# Sheet2.net
KiCad netlist of a schematic drawn in Altium Designer
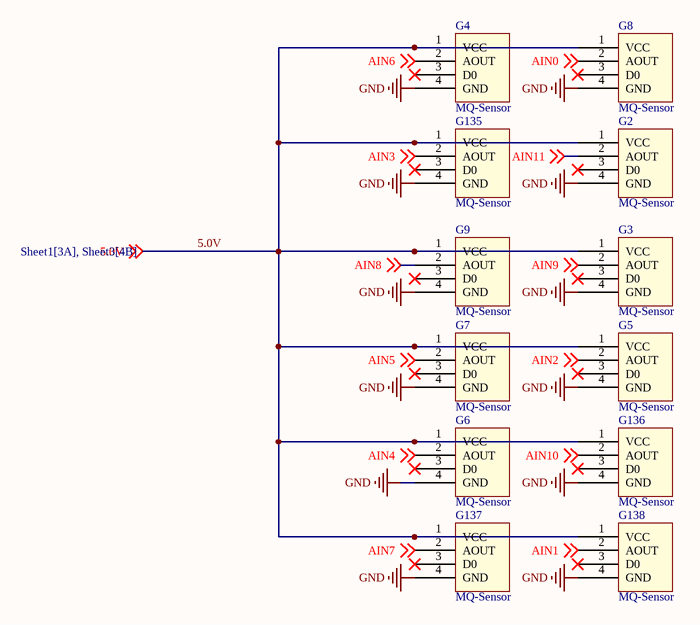
[diagram p0: Sheet2.SchDoc]

(export (version "E")
  (design (tool "Eeschema 10.0.6"))
  (components
    (comp (ref "G2")
      (value "MQ-Sensor")
      (footprint "MQ-FOOTPRINT-B")
      (libsource (lib "Schlib1") (part "MQ-Sensor"))
    )
    (comp (ref "G3")
      (value "MQ-Sensor")
      (footprint "MQ-FOOTPRINT-B")
      (libsource (lib "Schlib1") (part "MQ-Sensor"))
    )
    (comp (ref "G4")
      (value "MQ-Sensor")
      (footprint "MQ-FOOTPRINT-B")
      (libsource (lib "Schlib1") (part "MQ-Sensor"))
    )
    (comp (ref "G5")
      (value "MQ-Sensor")
      (footprint "MQ-FOOTPRINT-B")
      (libsource (lib "Schlib1") (part "MQ-Sensor"))
    )
    (comp (ref "G6")
      (value "MQ-Sensor")
      (footprint "MQ-FOOTPRINT-B")
      (libsource (lib "Schlib1") (part "MQ-Sensor"))
    )
    (comp (ref "G7")
      (value "MQ-Sensor")
      (footprint "MQ-FOOTPRINT-B")
      (libsource (lib "Schlib1") (part "MQ-Sensor"))
    )
    (comp (ref "G8")
      (value "MQ-Sensor")
      (footprint "MQ-FOOTPRINT-B")
      (libsource (lib "Schlib1") (part "MQ-Sensor"))
    )
    (comp (ref "G9")
      (value "MQ-Sensor")
      (footprint "MQ-FOOTPRINT-B")
      (libsource (lib "Schlib1") (part "MQ-Sensor"))
    )
    (comp (ref "G135")
      (value "MQ-Sensor")
      (footprint "MQ-FOOTPRINT-B")
      (libsource (lib "Schlib1") (part "MQ-Sensor"))
    )
    (comp (ref "G136")
      (value "MQ-Sensor")
      (footprint "MQ-Footprint-A")
      (libsource (lib "Schlib1") (part "MQ-Sensor"))
    )
    (comp (ref "G137")
      (value "MQ-Sensor")
      (footprint "MQ-Footprint-A")
      (libsource (lib "Schlib1") (part "MQ-Sensor"))
    )
    (comp (ref "G138")
      (value "MQ-Sensor")
      (footprint "MQ-FOOTPRINT-C")
      (libsource (lib "Schlib1") (part "MQ-Sensor"))
    )
  )
  (nets
    (net (code "1") (name "5.0V") (class "Default")
      (node (ref "G135") (pin "1") (pinfunction "VCC_1") (pintype "passive"))
      (node (ref "G136") (pin "1") (pinfunction "VCC_1") (pintype "passive"))
      (node (ref "G137") (pin "1") (pinfunction "VCC_1") (pintype "passive"))
      (node (ref "G138") (pin "1") (pinfunction "VCC_1") (pintype "passive"))
      (node (ref "G2") (pin "1") (pinfunction "VCC_1") (pintype "passive"))
      (node (ref "G3") (pin "1") (pinfunction "VCC_1") (pintype "passive"))
      (node (ref "G4") (pin "1") (pinfunction "VCC_1") (pintype "passive"))
      (node (ref "G5") (pin "1") (pinfunction "VCC_1") (pintype "passive"))
      (node (ref "G6") (pin "1") (pinfunction "VCC_1") (pintype "passive"))
      (node (ref "G7") (pin "1") (pinfunction "VCC_1") (pintype "passive"))
      (node (ref "G8") (pin "1") (pinfunction "VCC_1") (pintype "passive"))
      (node (ref "G9") (pin "1") (pinfunction "VCC_1") (pintype "passive"))
    )
    (net (code "2") (name "AIN0") (class "Default")
      (node (ref "G8") (pin "2") (pinfunction "AOUT_2") (pintype "passive"))
    )
    (net (code "3") (name "AIN1") (class "Default")
      (node (ref "G138") (pin "2") (pinfunction "AOUT_2") (pintype "passive"))
    )
    (net (code "4") (name "AIN2") (class "Default")
      (node (ref "G5") (pin "2") (pinfunction "AOUT_2") (pintype "passive"))
    )
    (net (code "5") (name "AIN3") (class "Default")
      (node (ref "G135") (pin "2") (pinfunction "AOUT_2") (pintype "passive"))
    )
    (net (code "6") (name "AIN4") (class "Default")
      (node (ref "G6") (pin "2") (pinfunction "AOUT_2") (pintype "passive"))
    )
    (net (code "7") (name "AIN5") (class "Default")
      (node (ref "G7") (pin "2") (pinfunction "AOUT_2") (pintype "passive"))
    )
    (net (code "8") (name "AIN6") (class "Default")
      (node (ref "G4") (pin "2") (pinfunction "AOUT_2") (pintype "passive"))
    )
    (net (code "9") (name "AIN7") (class "Default")
      (node (ref "G137") (pin "2") (pinfunction "AOUT_2") (pintype "passive"))
    )
    (net (code "10") (name "AIN8") (class "Default")
      (node (ref "G9") (pin "2") (pinfunction "AOUT_2") (pintype "passive"))
    )
    (net (code "11") (name "AIN9") (class "Default")
      (node (ref "G3") (pin "2") (pinfunction "AOUT_2") (pintype "passive"))
    )
    (net (code "12") (name "AIN10") (class "Default")
      (node (ref "G136") (pin "2") (pinfunction "AOUT_2") (pintype "passive"))
    )
    (net (code "13") (name "AIN11") (class "Default")
      (node (ref "G2") (pin "2") (pinfunction "AOUT_2") (pintype "passive"))
    )
    (net (code "14") (name "GND") (class "Default")
      (node (ref "G135") (pin "4") (pinfunction "GND_4") (pintype "passive"))
      (node (ref "G136") (pin "4") (pinfunction "GND_4") (pintype "passive"))
      (node (ref "G137") (pin "4") (pinfunction "GND_4") (pintype "passive"))
      (node (ref "G138") (pin "4") (pinfunction "GND_4") (pintype "passive"))
      (node (ref "G2") (pin "4") (pinfunction "GND_4") (pintype "passive"))
      (node (ref "G3") (pin "4") (pinfunction "GND_4") (pintype "passive"))
      (node (ref "G4") (pin "4") (pinfunction "GND_4") (pintype "passive"))
      (node (ref "G5") (pin "4") (pinfunction "GND_4") (pintype "passive"))
      (node (ref "G6") (pin "4") (pinfunction "GND_4") (pintype "passive"))
      (node (ref "G7") (pin "4") (pinfunction "GND_4") (pintype "passive"))
      (node (ref "G8") (pin "4") (pinfunction "GND_4") (pintype "passive"))
      (node (ref "G9") (pin "4") (pinfunction "GND_4") (pintype "passive"))
    )
    (net (code "15") (name "unconnected-(G2-D0-Pad3)") (class "Default")
      (node (ref "G2") (pin "3") (pinfunction "D0_3") (pintype "passive+no_connect"))
    )
    (net (code "16") (name "unconnected-(G3-D0-Pad3)") (class "Default")
      (node (ref "G3") (pin "3") (pinfunction "D0_3") (pintype "passive+no_connect"))
    )
    (net (code "17") (name "unconnected-(G4-D0-Pad3)") (class "Default")
      (node (ref "G4") (pin "3") (pinfunction "D0_3") (pintype "passive+no_connect"))
    )
    (net (code "18") (name "unconnected-(G5-D0-Pad3)") (class "Default")
      (node (ref "G5") (pin "3") (pinfunction "D0_3") (pintype "passive+no_connect"))
    )
    (net (code "19") (name "unconnected-(G6-D0-Pad3)") (class "Default")
      (node (ref "G6") (pin "3") (pinfunction "D0_3") (pintype "passive+no_connect"))
    )
    (net (code "20") (name "unconnected-(G7-D0-Pad3)") (class "Default")
      (node (ref "G7") (pin "3") (pinfunction "D0_3") (pintype "passive+no_connect"))
    )
    (net (code "21") (name "unconnected-(G8-D0-Pad3)") (class "Default")
      (node (ref "G8") (pin "3") (pinfunction "D0_3") (pintype "passive+no_connect"))
    )
    (net (code "22") (name "unconnected-(G9-D0-Pad3)") (class "Default")
      (node (ref "G9") (pin "3") (pinfunction "D0_3") (pintype "passive+no_connect"))
    )
    (net (code "23") (name "unconnected-(G135-D0-Pad3)") (class "Default")
      (node (ref "G135") (pin "3") (pinfunction "D0_3") (pintype "passive+no_connect"))
    )
    (net (code "24") (name "unconnected-(G136-D0-Pad3)") (class "Default")
      (node (ref "G136") (pin "3") (pinfunction "D0_3") (pintype "passive+no_connect"))
    )
    (net (code "25") (name "unconnected-(G137-D0-Pad3)") (class "Default")
      (node (ref "G137") (pin "3") (pinfunction "D0_3") (pintype "passive+no_connect"))
    )
    (net (code "26") (name "unconnected-(G138-D0-Pad3)") (class "Default")
      (node (ref "G138") (pin "3") (pinfunction "D0_3") (pintype "passive+no_connect"))
    )
  )
)
